# Fritzen_UM_r01_DRC_ok.net
KiCad netlist of a schematic drawn in EAGLE
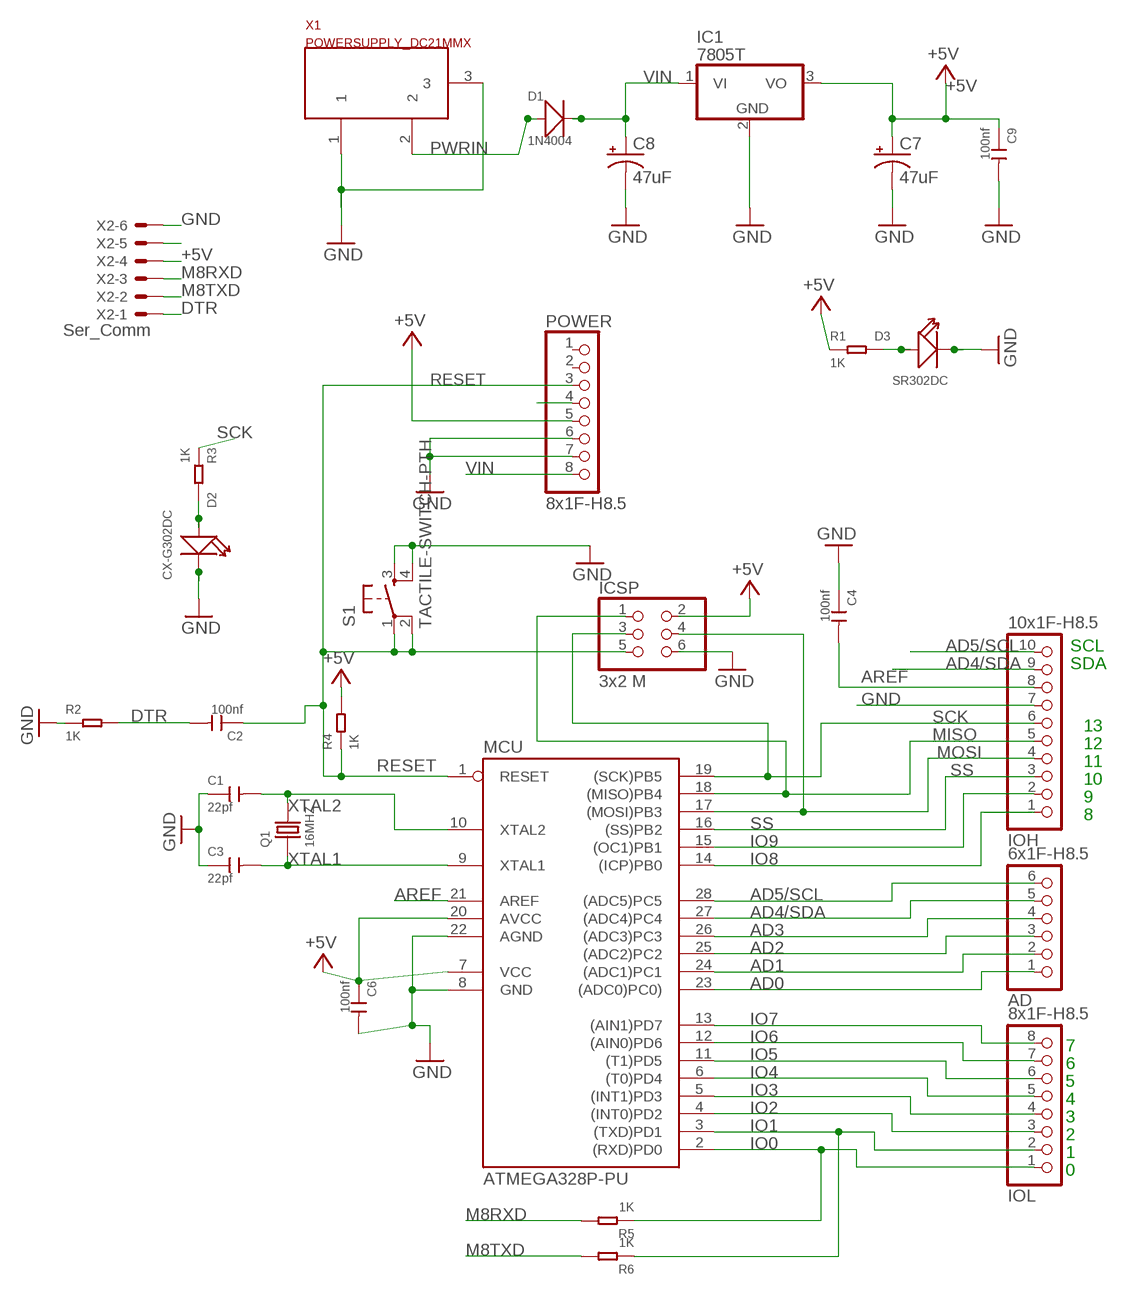
[diagram p0: schematic, sheet 1]

(export (version "E")
  (design (tool "Eeschema 10.0.6"))
  (components
    (comp (ref "AD")
      (value "6x1F-H8.5")
      (footprint "eagle-import:1X06")
      (libsource (lib "eagle-import") (part "PINHD-1X6"))
    )
    (comp (ref "C1")
      (value "22pf")
      (footprint "eagle-import:CERAMIC-2.54")
      (fields (field (name "MPN") "CS1-D5Y5V2A104ZSP"))
      (libsource (lib "eagle-import") (part "DIP-CERAMIC-DISC-22PF-50V-10%-NPO(D4.0MM)"))
    )
    (comp (ref "C2")
      (value "100nf")
      (footprint "eagle-import:CERAMIC-2.54")
      (fields (field (name "MPN") "CC1-F5SL2A101KSPW"))
      (libsource (lib "eagle-import") (part "DIP-CERAMIC-DISC-100NF-50V-Y5V(D5.0MM)"))
    )
    (comp (ref "C3")
      (value "22pf")
      (footprint "eagle-import:CERAMIC-2.54")
      (fields (field (name "MPN") "CS1-D5Y5V2A104ZSP"))
      (libsource (lib "eagle-import") (part "DIP-CERAMIC-DISC-22PF-50V-10%-NPO(D4.0MM)"))
    )
    (comp (ref "C4")
      (value "100nf")
      (footprint "eagle-import:CERAMIC-2.54")
      (fields (field (name "MPN") "CC1-F5SL2A101KSPW"))
      (libsource (lib "eagle-import") (part "DIP-CERAMIC-DISC-100NF-50V-Y5V(D5.0MM)"))
    )
    (comp (ref "C6")
      (value "100nf")
      (footprint "eagle-import:CERAMIC-2.54")
      (fields (field (name "MPN") "CC1-F5SL2A101KSPW"))
      (libsource (lib "eagle-import") (part "DIP-CERAMIC-DISC-100NF-50V-Y5V(D5.0MM)"))
    )
    (comp (ref "C7")
      (value "47uF")
      (footprint "eagle-import:E3,5-8")
      (libsource (lib "eagle-import") (part "CPOL-USE3.5-8"))
    )
    (comp (ref "C8")
      (value "47uF")
      (footprint "eagle-import:E3,5-8")
      (libsource (lib "eagle-import") (part "CPOL-USE3.5-8"))
    )
    (comp (ref "C9")
      (value "100nf")
      (footprint "eagle-import:CERAMIC-2.54")
      (fields (field (name "MPN") "CC1-F5SL2A101KSPW"))
      (libsource (lib "eagle-import") (part "DIP-CERAMIC-DISC-100NF-50V-Y5V(D5.0MM)"))
    )
    (comp (ref "D1")
      (value "1N4004")
      (footprint "eagle-import:DO-41")
      (libsource (lib "eagle-import") (part "DIP-DIODE-400V-1A(DO-41)"))
    )
    (comp (ref "D2")
      (value "CX-G302DC")
      (footprint "eagle-import:LED2-2.54-D3.0MM")
      (libsource (lib "eagle-import") (part "DIP-LED-GREEN-GREEN(2P-D3MM)"))
    )
    (comp (ref "D3")
      (value "SR302DC")
      (footprint "eagle-import:LED2-2.54-D3.0MM")
      (libsource (lib "eagle-import") (part "DIP-LED-RED-RED(2P-D3MM)"))
    )
    (comp (ref "IC1")
      (value "7805T")
      (footprint "eagle-import:TO220H")
      (libsource (lib "eagle-import") (part "78T05"))
    )
    (comp (ref "ICSP")
      (value "3x2 M")
      (footprint "eagle-import:2X03")
      (libsource (lib "eagle-import") (part "PINHD-2X3"))
    )
    (comp (ref "IOH")
      (value "10x1F-H8.5")
      (footprint "eagle-import:1X10")
      (libsource (lib "eagle-import") (part "PINHD-1X10_ARD"))
    )
    (comp (ref "IOL")
      (value "8x1F-H8.5")
      (footprint "eagle-import:1X08")
      (libsource (lib "eagle-import") (part "PINHD-1X8"))
    )
    (comp (ref "MCU")
      (value "ATMEGA328P-PU")
      (footprint "eagle-import:DIL28-3")
      (libsource (lib "eagle-import") (part "ATMEGA328P-PU"))
    )
    (comp (ref "POWER")
      (value "8x1F-H8.5")
      (footprint "eagle-import:1X08")
      (libsource (lib "eagle-import") (part "PINHD-1X8"))
    )
    (comp (ref "Q1")
      (value "16MHZ")
      (footprint "eagle-import:HC49US")
      (fields (field (name "MPN") "49S/18PF"))
      (libsource (lib "eagle-import") (part "DIP-CRYSTAL-16MHZ-18PF-30PPM-50R(HC49US)"))
    )
    (comp (ref "R1")
      (value "1K")
      (footprint "eagle-import:PR-D2.3XL6.5MM")
      (fields (field (name "MPN") "FHCFR-1/4W-102J"))
      (libsource (lib "eagle-import") (part "DIP-RES-1K-5%-1/4W(PR-D2.3XL6.5MM)"))
    )
    (comp (ref "R2")
      (value "1K")
      (footprint "eagle-import:PR-D2.3XL6.5MM")
      (fields (field (name "MPN") "FHCFR-1/4W-102J"))
      (libsource (lib "eagle-import") (part "DIP-RES-1K-5%-1/4W(PR-D2.3XL6.5MM)"))
    )
    (comp (ref "R3")
      (value "1K")
      (footprint "eagle-import:PR-D2.3XL6.5MM")
      (fields (field (name "MPN") "FHCFR-1/4W-102J"))
      (libsource (lib "eagle-import") (part "DIP-RES-1K-5%-1/4W(PR-D2.3XL6.5MM)"))
    )
    (comp (ref "R4")
      (value "1K")
      (footprint "eagle-import:PR-D2.3XL6.5MM")
      (fields (field (name "MPN") "FHCFR-1/4W-102J"))
      (libsource (lib "eagle-import") (part "DIP-RES-1K-5%-1/4W(PR-D2.3XL6.5MM)"))
    )
    (comp (ref "R5")
      (value "1K")
      (footprint "eagle-import:PR-D2.3XL6.5MM")
      (fields (field (name "MPN") "FHCFR-1/4W-102J"))
      (libsource (lib "eagle-import") (part "DIP-RES-1K-5%-1/4W(PR-D2.3XL6.5MM)"))
    )
    (comp (ref "R6")
      (value "1K")
      (footprint "eagle-import:PR-D2.3XL6.5MM")
      (fields (field (name "MPN") "FHCFR-1/4W-102J"))
      (libsource (lib "eagle-import") (part "DIP-RES-1K-5%-1/4W(PR-D2.3XL6.5MM)"))
    )
    (comp (ref "S1")
      (value "TACTILE-SWITCH-PTH")
      (footprint "eagle-import:TAC-SWITCH-PTH")
      (libsource (lib "eagle-import") (part "TACTILE-SWITCH-PTH"))
    )
    (comp (ref "X1")
      (value "POWERSUPPLY_DC21MMX")
      (footprint "eagle-import:POWERSUPPLY_DC-21MM")
      (libsource (lib "eagle-import") (part "POWERSUPPLY_DC21MMX"))
    )
    (comp (ref "X2")
      (value "Ser_Comm")
      (footprint "eagle-import:22-23-2061")
      (fields (field (name "MF") "MOLEX") (field (name "MPN") "22-23-2061"))
      (libsource (lib "eagle-import") (part "22-23-2061"))
    )
  )
  (nets
    (net (code "1") (name "+5V") (class "Default")
      (node (ref "C6") (pin "1") (pinfunction "1_1") (pintype "passive"))
      (node (ref "C7") (pin "+") (pinfunction "+_+") (pintype "passive"))
      (node (ref "C9") (pin "1") (pinfunction "1_1") (pintype "passive"))
      (node (ref "IC1") (pin "3") (pinfunction "VO_3") (pintype "passive"))
      (node (ref "ICSP") (pin "2") (pinfunction "2_2") (pintype "passive"))
      (node (ref "MCU") (pin "20") (pinfunction "AVCC_20") (pintype "power_in"))
      (node (ref "MCU") (pin "7") (pinfunction "VCC_7") (pintype "power_in"))
      (node (ref "POWER") (pin "5") (pinfunction "5_5") (pintype "passive"))
      (node (ref "R1") (pin "1") (pinfunction "1_1") (pintype "passive"))
      (node (ref "R4") (pin "2") (pinfunction "2_2") (pintype "passive"))
      (node (ref "X2") (pin "4") (pinfunction "S_4") (pintype "passive"))
    )
    (net (code "2") (name "/AD0") (class "Default")
      (node (ref "AD") (pin "1") (pinfunction "1_1") (pintype "passive"))
      (node (ref "MCU") (pin "23") (pinfunction "(ADC0)PC0)_23") (pintype "bidirectional"))
    )
    (net (code "3") (name "/AD1") (class "Default")
      (node (ref "AD") (pin "2") (pinfunction "2_2") (pintype "passive"))
      (node (ref "MCU") (pin "24") (pinfunction "(ADC1)PC1_24") (pintype "bidirectional"))
    )
    (net (code "4") (name "/AD2") (class "Default")
      (node (ref "AD") (pin "3") (pinfunction "3_3") (pintype "passive"))
      (node (ref "MCU") (pin "25") (pinfunction "(ADC2)PC2_25") (pintype "bidirectional"))
    )
    (net (code "5") (name "/AD3") (class "Default")
      (node (ref "AD") (pin "4") (pinfunction "4_4") (pintype "passive"))
      (node (ref "MCU") (pin "26") (pinfunction "(ADC3)PC3_26") (pintype "bidirectional"))
    )
    (net (code "6") (name "/AD4{slash}SDA") (class "Default")
      (node (ref "AD") (pin "5") (pinfunction "5_5") (pintype "passive"))
      (node (ref "IOH") (pin "9") (pinfunction "9_9") (pintype "passive"))
      (node (ref "MCU") (pin "27") (pinfunction "(ADC4)PC4_27") (pintype "bidirectional"))
    )
    (net (code "7") (name "/AD5{slash}SCL") (class "Default")
      (node (ref "AD") (pin "6") (pinfunction "6_6") (pintype "passive"))
      (node (ref "IOH") (pin "10") (pinfunction "10_10") (pintype "passive"))
      (node (ref "MCU") (pin "28") (pinfunction "(ADC5)PC5_28") (pintype "bidirectional"))
    )
    (net (code "8") (name "/AREF") (class "Default")
      (node (ref "C4") (pin "2") (pinfunction "2_2") (pintype "passive"))
      (node (ref "IOH") (pin "8") (pinfunction "8_8") (pintype "passive"))
      (node (ref "MCU") (pin "21") (pinfunction "AREF_21") (pintype "passive"))
    )
    (net (code "9") (name "/DTR") (class "Default")
      (node (ref "C2") (pin "2") (pinfunction "2_2") (pintype "passive"))
      (node (ref "R2") (pin "2") (pinfunction "2_2") (pintype "passive"))
      (node (ref "X2") (pin "1") (pinfunction "S_1") (pintype "passive"))
    )
    (net (code "10") (name "/IO0") (class "Default")
      (node (ref "IOL") (pin "1") (pinfunction "1_1") (pintype "passive"))
      (node (ref "MCU") (pin "2") (pinfunction "(RXD)PD0_2") (pintype "bidirectional"))
      (node (ref "R5") (pin "1") (pinfunction "1_1") (pintype "passive"))
    )
    (net (code "11") (name "/IO1") (class "Default")
      (node (ref "IOL") (pin "2") (pinfunction "2_2") (pintype "passive"))
      (node (ref "MCU") (pin "3") (pinfunction "(TXD)PD1_3") (pintype "bidirectional"))
      (node (ref "R6") (pin "1") (pinfunction "1_1") (pintype "passive"))
    )
    (net (code "12") (name "/IO2") (class "Default")
      (node (ref "IOL") (pin "3") (pinfunction "3_3") (pintype "passive"))
      (node (ref "MCU") (pin "4") (pinfunction "(INT0)PD2_4") (pintype "bidirectional"))
    )
    (net (code "13") (name "/IO3") (class "Default")
      (node (ref "IOL") (pin "4") (pinfunction "4_4") (pintype "passive"))
      (node (ref "MCU") (pin "5") (pinfunction "(INT1)PD3_5") (pintype "bidirectional"))
    )
    (net (code "14") (name "/IO4") (class "Default")
      (node (ref "IOL") (pin "5") (pinfunction "5_5") (pintype "passive"))
      (node (ref "MCU") (pin "6") (pinfunction "(T0)PD4_6") (pintype "bidirectional"))
    )
    (net (code "15") (name "/IO5") (class "Default")
      (node (ref "IOL") (pin "6") (pinfunction "6_6") (pintype "passive"))
      (node (ref "MCU") (pin "11") (pinfunction "(T1)PD5_11") (pintype "bidirectional"))
    )
    (net (code "16") (name "/IO6") (class "Default")
      (node (ref "IOL") (pin "7") (pinfunction "7_7") (pintype "passive"))
      (node (ref "MCU") (pin "12") (pinfunction "(AIN0)PD6_12") (pintype "bidirectional"))
    )
    (net (code "17") (name "/IO7") (class "Default")
      (node (ref "IOL") (pin "8") (pinfunction "8_8") (pintype "passive"))
      (node (ref "MCU") (pin "13") (pinfunction "(AIN1)PD7_13") (pintype "bidirectional"))
    )
    (net (code "18") (name "/IO8") (class "Default")
      (node (ref "IOH") (pin "1") (pinfunction "1_1") (pintype "passive"))
      (node (ref "MCU") (pin "14") (pinfunction "(ICP)PB0_14") (pintype "bidirectional"))
    )
    (net (code "19") (name "/IO9") (class "Default")
      (node (ref "IOH") (pin "2") (pinfunction "2_2") (pintype "passive"))
      (node (ref "MCU") (pin "15") (pinfunction "(OC1)PB1_15") (pintype "bidirectional"))
    )
    (net (code "20") (name "/M8RXD") (class "Default")
      (node (ref "R5") (pin "2") (pinfunction "2_2") (pintype "passive"))
      (node (ref "X2") (pin "3") (pinfunction "S_3") (pintype "passive"))
    )
    (net (code "21") (name "/M8TXD") (class "Default")
      (node (ref "R6") (pin "2") (pinfunction "2_2") (pintype "passive"))
      (node (ref "X2") (pin "2") (pinfunction "S_2") (pintype "passive"))
    )
    (net (code "22") (name "/MISO") (class "Default")
      (node (ref "ICSP") (pin "1") (pinfunction "1_1") (pintype "passive"))
      (node (ref "IOH") (pin "5") (pinfunction "5_5") (pintype "passive"))
      (node (ref "MCU") (pin "18") (pinfunction "(MISO)PB4_18") (pintype "bidirectional"))
    )
    (net (code "23") (name "/MOSI") (class "Default")
      (node (ref "ICSP") (pin "4") (pinfunction "4_4") (pintype "passive"))
      (node (ref "IOH") (pin "4") (pinfunction "4_4") (pintype "passive"))
      (node (ref "MCU") (pin "17") (pinfunction "(MOSI)PB3_17") (pintype "bidirectional"))
    )
    (net (code "24") (name "/PWRIN") (class "Default")
      (node (ref "D1") (pin "1") (pinfunction "+_1") (pintype "passive"))
      (node (ref "X1") (pin "2") (pinfunction "2_2") (pintype "power_in"))
    )
    (net (code "25") (name "/RESET") (class "Default")
      (node (ref "C2") (pin "1") (pinfunction "1_1") (pintype "passive"))
      (node (ref "ICSP") (pin "5") (pinfunction "5_5") (pintype "passive"))
      (node (ref "MCU") (pin "1") (pinfunction "RESET_1") (pintype "input"))
      (node (ref "POWER") (pin "3") (pinfunction "3_3") (pintype "passive"))
      (node (ref "R4") (pin "1") (pinfunction "1_1") (pintype "passive"))
      (node (ref "S1") (pin "1") (pinfunction "1_1") (pintype "passive"))
      (node (ref "S1") (pin "2") (pinfunction "2_2") (pintype "passive"))
    )
    (net (code "26") (name "/SCK") (class "Default")
      (node (ref "ICSP") (pin "3") (pinfunction "3_3") (pintype "passive"))
      (node (ref "IOH") (pin "6") (pinfunction "6_6") (pintype "passive"))
      (node (ref "MCU") (pin "19") (pinfunction "(SCK)PB5_19") (pintype "bidirectional"))
      (node (ref "R3") (pin "1") (pinfunction "1_1") (pintype "passive"))
    )
    (net (code "27") (name "/SS") (class "Default")
      (node (ref "IOH") (pin "3") (pinfunction "3_3") (pintype "passive"))
      (node (ref "MCU") (pin "16") (pinfunction "(SS)PB2_16") (pintype "bidirectional"))
    )
    (net (code "28") (name "/VIN") (class "Default")
      (node (ref "C8") (pin "+") (pinfunction "+_+") (pintype "passive"))
      (node (ref "D1") (pin "2") (pinfunction "-_2") (pintype "passive"))
      (node (ref "IC1") (pin "1") (pinfunction "VI_1") (pintype "input"))
      (node (ref "POWER") (pin "8") (pinfunction "8_8") (pintype "passive"))
    )
    (net (code "29") (name "/XTAL1") (class "Default")
      (node (ref "C3") (pin "2") (pinfunction "2_2") (pintype "passive"))
      (node (ref "MCU") (pin "9") (pinfunction "XTAL1_9") (pintype "bidirectional"))
      (node (ref "Q1") (pin "1") (pinfunction "1_1") (pintype "passive"))
    )
    (net (code "30") (name "/XTAL2") (class "Default")
      (node (ref "C1") (pin "2") (pinfunction "2_2") (pintype "passive"))
      (node (ref "MCU") (pin "10") (pinfunction "XTAL2_10") (pintype "bidirectional"))
      (node (ref "Q1") (pin "2") (pinfunction "2_2") (pintype "passive"))
    )
    (net (code "31") (name "GND") (class "Default")
      (node (ref "C1") (pin "1") (pinfunction "1_1") (pintype "passive"))
      (node (ref "C3") (pin "1") (pinfunction "1_1") (pintype "passive"))
      (node (ref "C4") (pin "1") (pinfunction "1_1") (pintype "passive"))
      (node (ref "C6") (pin "2") (pinfunction "2_2") (pintype "passive"))
      (node (ref "C7") (pin "-") (pinfunction "-_-") (pintype "passive"))
      (node (ref "C8") (pin "-") (pinfunction "-_-") (pintype "passive"))
      (node (ref "C9") (pin "2") (pinfunction "2_2") (pintype "passive"))
      (node (ref "D2") (pin "K") (pinfunction "-_K") (pintype "passive"))
      (node (ref "D3") (pin "K") (pinfunction "-_K") (pintype "passive"))
      (node (ref "IC1") (pin "2") (pinfunction "GND_2") (pintype "passive"))
      (node (ref "ICSP") (pin "6") (pinfunction "6_6") (pintype "passive"))
      (node (ref "IOH") (pin "7") (pinfunction "7_7") (pintype "passive"))
      (node (ref "MCU") (pin "22") (pinfunction "AGND_22") (pintype "power_in"))
      (node (ref "MCU") (pin "8") (pinfunction "GND_8") (pintype "power_in"))
      (node (ref "POWER") (pin "6") (pinfunction "6_6") (pintype "passive"))
      (node (ref "POWER") (pin "7") (pinfunction "7_7") (pintype "passive"))
      (node (ref "R2") (pin "1") (pinfunction "1_1") (pintype "passive"))
      (node (ref "S1") (pin "3") (pinfunction "3_3") (pintype "passive"))
      (node (ref "S1") (pin "4") (pinfunction "4_4") (pintype "passive"))
      (node (ref "X1") (pin "1") (pinfunction "1_1") (pintype "power_in"))
      (node (ref "X1") (pin "3") (pinfunction "3_3") (pintype "power_in"))
      (node (ref "X2") (pin "6") (pinfunction "S_6") (pintype "passive"))
    )
    (net (code "32") (name "Net-(D2-+)") (class "Default")
      (node (ref "D2") (pin "A") (pinfunction "+_A") (pintype "passive"))
      (node (ref "R3") (pin "2") (pinfunction "2_2") (pintype "passive"))
    )
    (net (code "33") (name "Net-(D3-+)") (class "Default")
      (node (ref "D3") (pin "A") (pinfunction "+_A") (pintype "passive"))
      (node (ref "R1") (pin "2") (pinfunction "2_2") (pintype "passive"))
    )
    (net (code "34") (name "unconnected-(POWER-Pad1)") (class "Default")
      (node (ref "POWER") (pin "1") (pinfunction "1_1") (pintype "passive"))
    )
    (net (code "35") (name "unconnected-(POWER-Pad2)") (class "Default")
      (node (ref "POWER") (pin "2") (pinfunction "2_2") (pintype "passive"))
    )
    (net (code "36") (name "unconnected-(POWER-Pad4)") (class "Default")
      (node (ref "POWER") (pin "4") (pinfunction "4_4") (pintype "passive"))
    )
    (net (code "37") (name "unconnected-(X2E-S-Pad5)") (class "Default")
      (node (ref "X2") (pin "5") (pinfunction "S_5") (pintype "passive"))
    )
  )
)
